# Apollo4-BluePlus-Module_rev_b_v6.net
KiCad netlist of a schematic drawn in EAGLE
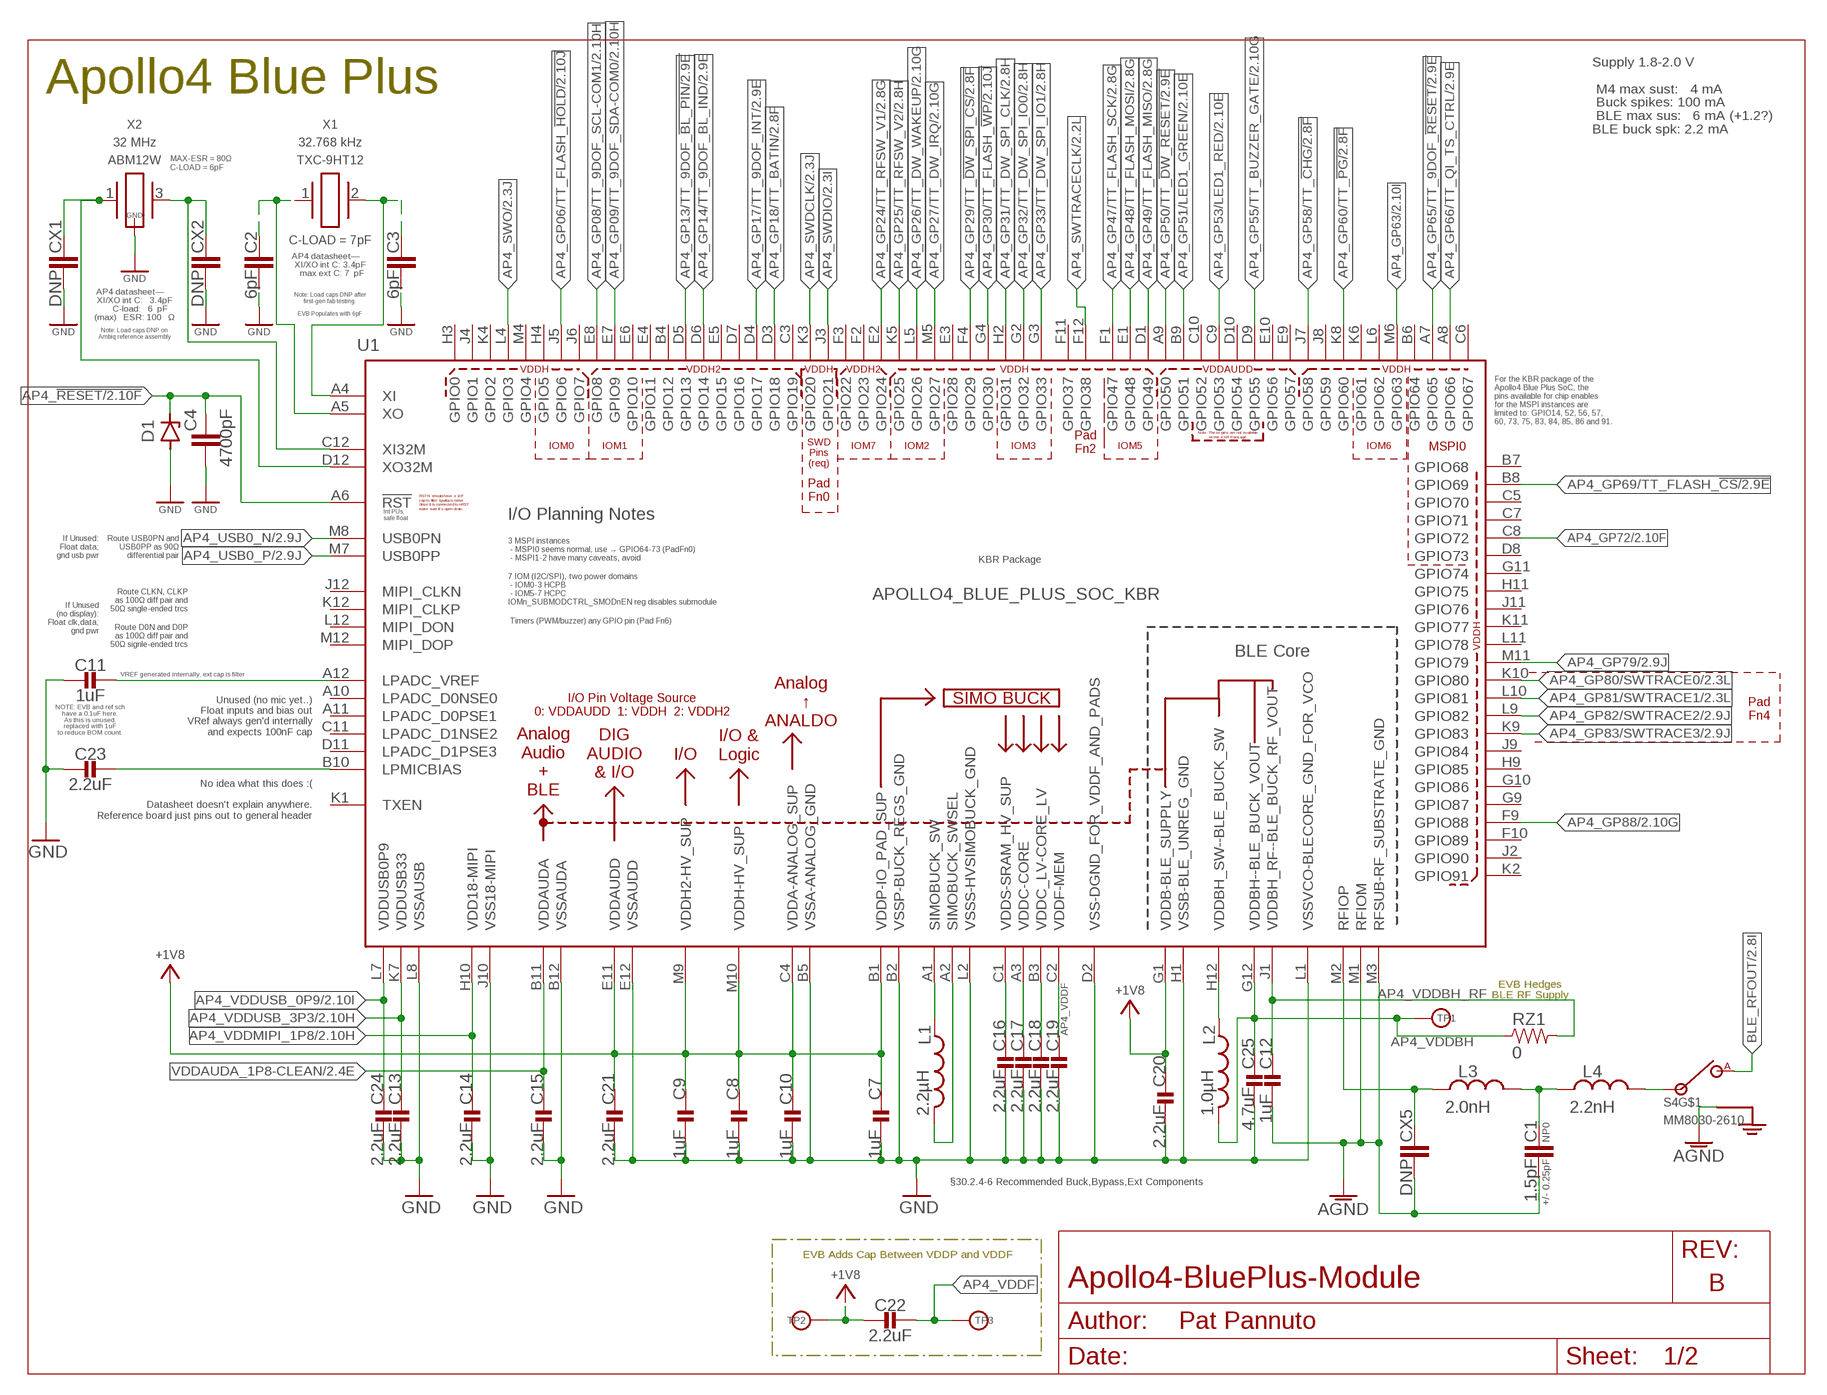
[diagram p0: schematic, sheet 1]
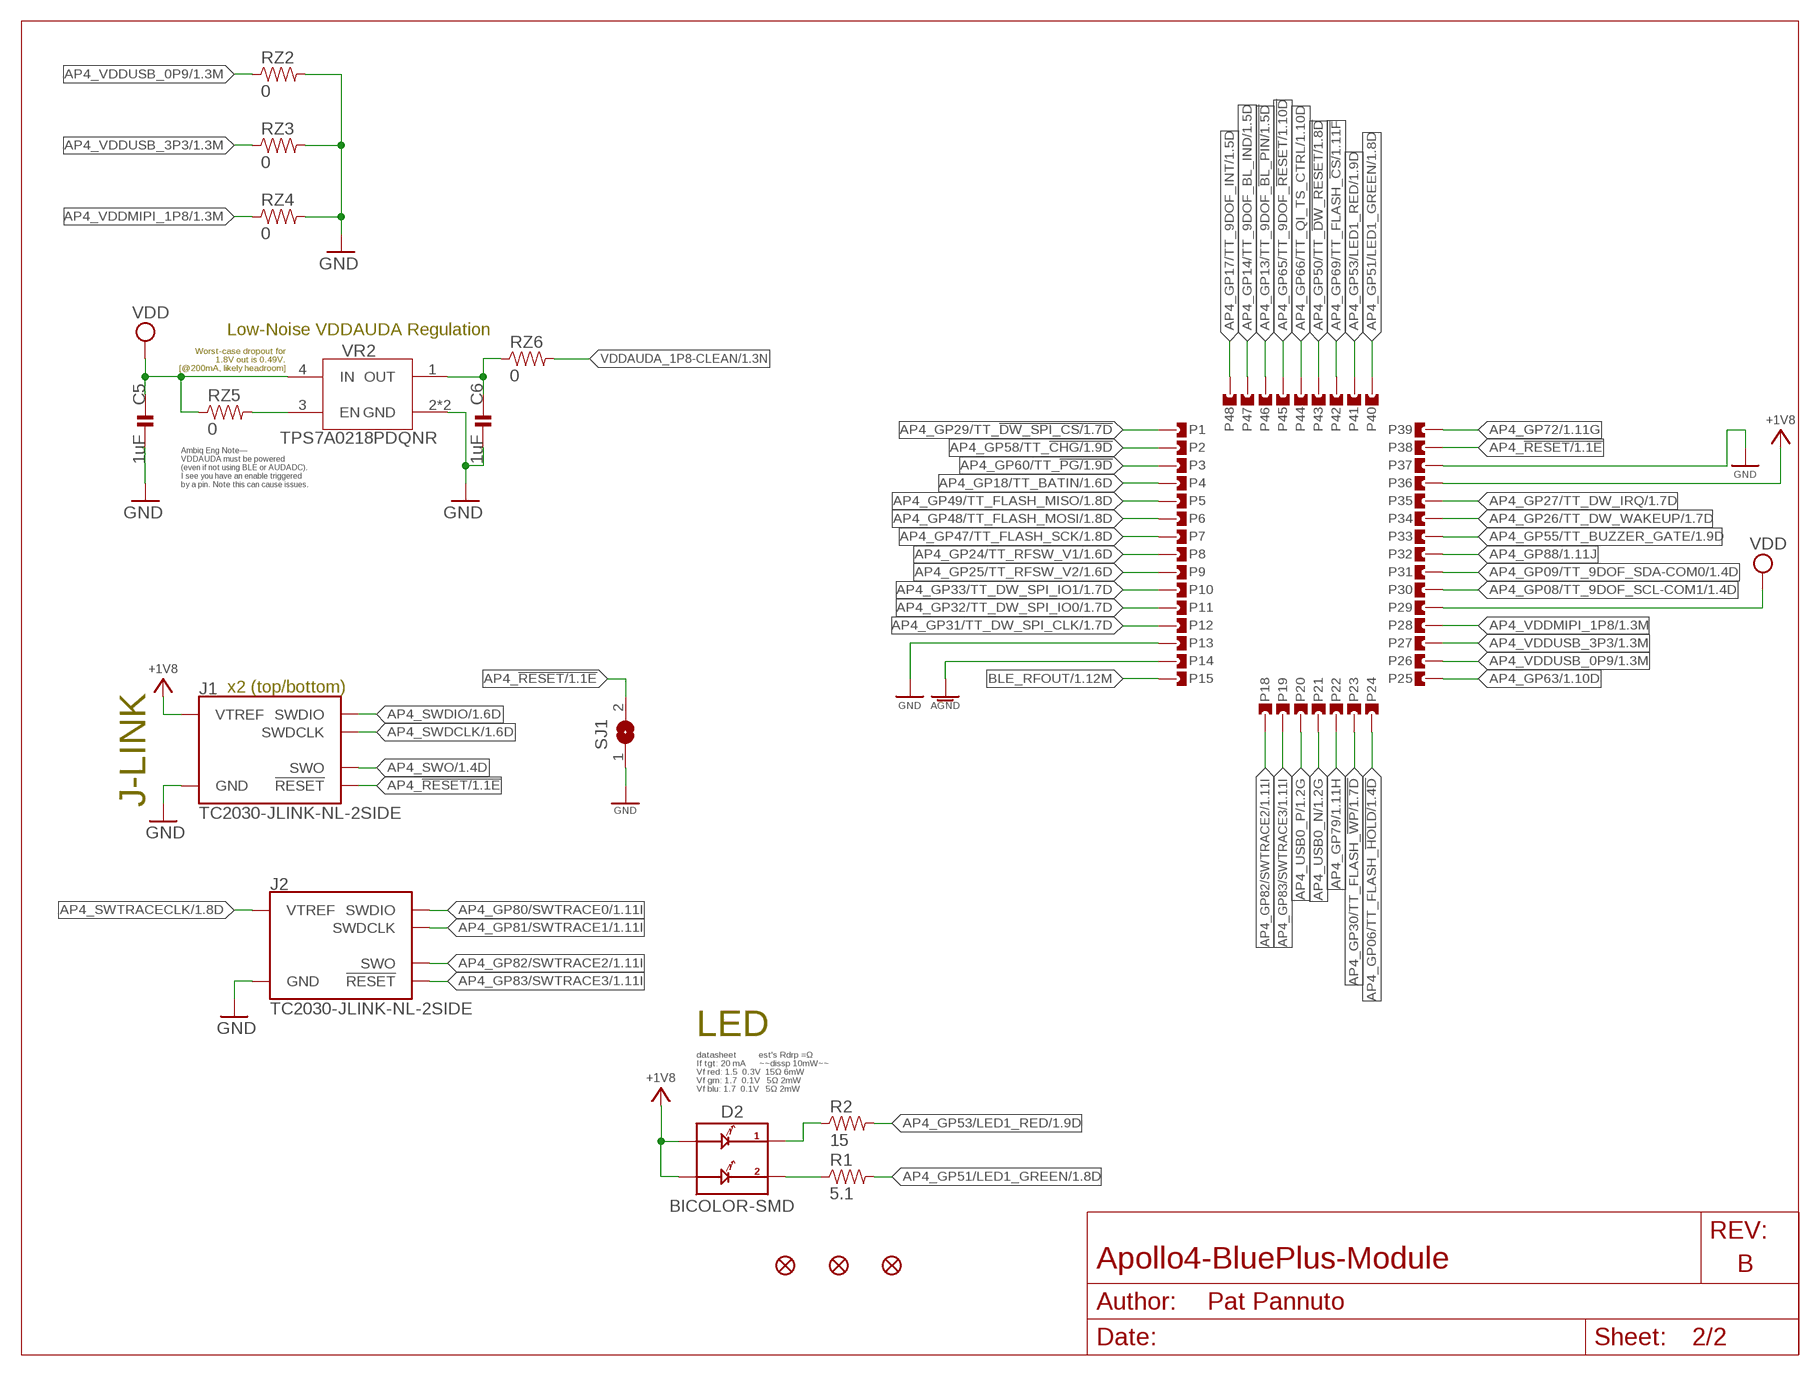
[diagram p1: schematic, sheet 2]

(export (version "E")
  (design (tool "Eeschema 10.0.6"))
  (components
    (comp (ref "C5")
      (value "1uF")
      (footprint "eagle-import:0201_CAP")
      (fields (field (name "MANUFACTURER") "Murata") (field (name "MPN") "GRM033R61A105ME44D"))
      (libsource (lib "eagle-import") (part "passives_20904581_CAPACITOR0201_CAP"))
    )
    (comp (ref "C6")
      (value "1uF")
      (footprint "eagle-import:0201_CAP")
      (fields (field (name "MANUFACTURER") "Murata") (field (name "MPN") "GRM033R61A105ME44D"))
      (libsource (lib "eagle-import") (part "passives_20904581_CAPACITOR0201_CAP"))
    )
    (comp (ref "D2")
      (value "BICOLOR-SMD")
      (footprint "eagle-import:LED-0606")
      (fields (field (name "MPN") "MCL0606FRD1GR1T"))
      (libsource (lib "eagle-import") (part "BICOLOR-SMD"))
    )
    (comp (ref "FD1")
      (value "FIDUCIALUFIDUCIAL")
      (footprint "eagle-import:FIDUCIAL-MICRO")
      (libsource (lib "eagle-import") (part "FIDUCIALUFIDUCIAL"))
    )
    (comp (ref "FD2")
      (value "FIDUCIALUFIDUCIAL")
      (footprint "eagle-import:FIDUCIAL-MICRO")
      (libsource (lib "eagle-import") (part "FIDUCIALUFIDUCIAL"))
    )
    (comp (ref "FD3")
      (value "FIDUCIALUFIDUCIAL")
      (footprint "eagle-import:FIDUCIAL-MICRO")
      (libsource (lib "eagle-import") (part "FIDUCIALUFIDUCIAL"))
    )
    (comp (ref "J1")
      (value "TC2030-JLINK-NL-2SIDE")
      (footprint "eagle-import:TC2030-IDC-NL-2SIDE")
      (libsource (lib "eagle-import") (part "TC2030-JLINK-NL-2SIDE"))
    )
    (comp (ref "J2")
      (value "TC2030-JLINK-NL-2SIDE")
      (footprint "eagle-import:TC2030-IDC-NL-2SIDE")
      (libsource (lib "eagle-import") (part "TC2030-JLINK-NL-2SIDE"))
    )
    (comp (ref "P1")
      (value "CASTELLATION4L")
      (footprint "eagle-import:CASTELLATION-0.55MM_DRILL-4L")
      (libsource (lib "eagle-import") (part "CASTELLATION4L"))
    )
    (comp (ref "P2")
      (value "CASTELLATION4L")
      (footprint "eagle-import:CASTELLATION-0.55MM_DRILL-4L")
      (libsource (lib "eagle-import") (part "CASTELLATION4L"))
    )
    (comp (ref "P3")
      (value "CASTELLATION4L")
      (footprint "eagle-import:CASTELLATION-0.55MM_DRILL-4L")
      (libsource (lib "eagle-import") (part "CASTELLATION4L"))
    )
    (comp (ref "P4")
      (value "CASTELLATION4L")
      (footprint "eagle-import:CASTELLATION-0.55MM_DRILL-4L")
      (libsource (lib "eagle-import") (part "CASTELLATION4L"))
    )
    (comp (ref "P5")
      (value "CASTELLATION4L")
      (footprint "eagle-import:CASTELLATION-0.55MM_DRILL-4L")
      (libsource (lib "eagle-import") (part "CASTELLATION4L"))
    )
    (comp (ref "P6")
      (value "CASTELLATION4L")
      (footprint "eagle-import:CASTELLATION-0.55MM_DRILL-4L")
      (libsource (lib "eagle-import") (part "CASTELLATION4L"))
    )
    (comp (ref "P7")
      (value "CASTELLATION4L")
      (footprint "eagle-import:CASTELLATION-0.55MM_DRILL-4L")
      (libsource (lib "eagle-import") (part "CASTELLATION4L"))
    )
    (comp (ref "P8")
      (value "CASTELLATION4L")
      (footprint "eagle-import:CASTELLATION-0.55MM_DRILL-4L")
      (libsource (lib "eagle-import") (part "CASTELLATION4L"))
    )
    (comp (ref "P9")
      (value "CASTELLATION4L")
      (footprint "eagle-import:CASTELLATION-0.55MM_DRILL-4L")
      (libsource (lib "eagle-import") (part "CASTELLATION4L"))
    )
    (comp (ref "P10")
      (value "CASTELLATION4L")
      (footprint "eagle-import:CASTELLATION-0.55MM_DRILL-4L")
      (libsource (lib "eagle-import") (part "CASTELLATION4L"))
    )
    (comp (ref "P11")
      (value "CASTELLATION4L")
      (footprint "eagle-import:CASTELLATION-0.55MM_DRILL-4L")
      (libsource (lib "eagle-import") (part "CASTELLATION4L"))
    )
    (comp (ref "P12")
      (value "CASTELLATION4L")
      (footprint "eagle-import:CASTELLATION-0.55MM_DRILL-4L")
      (libsource (lib "eagle-import") (part "CASTELLATION4L"))
    )
    (comp (ref "P13")
      (value "CASTELLATION4L")
      (footprint "eagle-import:CASTELLATION-0.55MM_DRILL-4L")
      (libsource (lib "eagle-import") (part "CASTELLATION4L"))
    )
    (comp (ref "P14")
      (value "CASTELLATION4L")
      (footprint "eagle-import:CASTELLATION-0.55MM_DRILL-4L")
      (libsource (lib "eagle-import") (part "CASTELLATION4L"))
    )
    (comp (ref "P15")
      (value "CASTELLATION4L")
      (footprint "eagle-import:CASTELLATION-0.55MM_DRILL-4L")
      (libsource (lib "eagle-import") (part "CASTELLATION4L"))
    )
    (comp (ref "P18")
      (value "CASTELLATION4L")
      (footprint "eagle-import:CASTELLATION-0.55MM_DRILL-4L")
      (libsource (lib "eagle-import") (part "CASTELLATION4L"))
    )
    (comp (ref "P19")
      (value "CASTELLATION4L")
      (footprint "eagle-import:CASTELLATION-0.55MM_DRILL-4L")
      (libsource (lib "eagle-import") (part "CASTELLATION4L"))
    )
    (comp (ref "P20")
      (value "CASTELLATION4L")
      (footprint "eagle-import:CASTELLATION-0.55MM_DRILL-4L")
      (libsource (lib "eagle-import") (part "CASTELLATION4L"))
    )
    (comp (ref "P21")
      (value "CASTELLATION4L")
      (footprint "eagle-import:CASTELLATION-0.55MM_DRILL-4L")
      (libsource (lib "eagle-import") (part "CASTELLATION4L"))
    )
    (comp (ref "P22")
      (value "CASTELLATION4L")
      (footprint "eagle-import:CASTELLATION-0.55MM_DRILL-4L")
      (libsource (lib "eagle-import") (part "CASTELLATION4L"))
    )
    (comp (ref "P23")
      (value "CASTELLATION4L")
      (footprint "eagle-import:CASTELLATION-0.55MM_DRILL-4L")
      (libsource (lib "eagle-import") (part "CASTELLATION4L"))
    )
    (comp (ref "P24")
      (value "CASTELLATION4L")
      (footprint "eagle-import:CASTELLATION-0.55MM_DRILL-4L")
      (libsource (lib "eagle-import") (part "CASTELLATION4L"))
    )
    (comp (ref "P25")
      (value "CASTELLATION4L")
      (footprint "eagle-import:CASTELLATION-0.55MM_DRILL-4L")
      (libsource (lib "eagle-import") (part "CASTELLATION4L"))
    )
    (comp (ref "P26")
      (value "CASTELLATION4L")
      (footprint "eagle-import:CASTELLATION-0.55MM_DRILL-4L")
      (libsource (lib "eagle-import") (part "CASTELLATION4L"))
    )
    (comp (ref "P27")
      (value "CASTELLATION4L")
      (footprint "eagle-import:CASTELLATION-0.55MM_DRILL-4L")
      (libsource (lib "eagle-import") (part "CASTELLATION4L"))
    )
    (comp (ref "P28")
      (value "CASTELLATION4L")
      (footprint "eagle-import:CASTELLATION-0.55MM_DRILL-4L")
      (libsource (lib "eagle-import") (part "CASTELLATION4L"))
    )
    (comp (ref "P29")
      (value "CASTELLATION4L")
      (footprint "eagle-import:CASTELLATION-0.55MM_DRILL-4L")
      (libsource (lib "eagle-import") (part "CASTELLATION4L"))
    )
    (comp (ref "P30")
      (value "CASTELLATION4L")
      (footprint "eagle-import:CASTELLATION-0.55MM_DRILL-4L")
      (libsource (lib "eagle-import") (part "CASTELLATION4L"))
    )
    (comp (ref "P31")
      (value "CASTELLATION4L")
      (footprint "eagle-import:CASTELLATION-0.55MM_DRILL-4L")
      (libsource (lib "eagle-import") (part "CASTELLATION4L"))
    )
    (comp (ref "P32")
      (value "CASTELLATION4L")
      (footprint "eagle-import:CASTELLATION-0.55MM_DRILL-4L")
      (libsource (lib "eagle-import") (part "CASTELLATION4L"))
    )
    (comp (ref "P33")
      (value "CASTELLATION4L")
      (footprint "eagle-import:CASTELLATION-0.55MM_DRILL-4L")
      (libsource (lib "eagle-import") (part "CASTELLATION4L"))
    )
    (comp (ref "P34")
      (value "CASTELLATION4L")
      (footprint "eagle-import:CASTELLATION-0.55MM_DRILL-4L")
      (libsource (lib "eagle-import") (part "CASTELLATION4L"))
    )
    (comp (ref "P35")
      (value "CASTELLATION4L")
      (footprint "eagle-import:CASTELLATION-0.55MM_DRILL-4L")
      (libsource (lib "eagle-import") (part "CASTELLATION4L"))
    )
    (comp (ref "P36")
      (value "CASTELLATION4L")
      (footprint "eagle-import:CASTELLATION-0.55MM_DRILL-4L")
      (libsource (lib "eagle-import") (part "CASTELLATION4L"))
    )
    (comp (ref "P37")
      (value "CASTELLATION4L")
      (footprint "eagle-import:CASTELLATION-0.55MM_DRILL-4L")
      (libsource (lib "eagle-import") (part "CASTELLATION4L"))
    )
    (comp (ref "P38")
      (value "CASTELLATION4L")
      (footprint "eagle-import:CASTELLATION-0.55MM_DRILL-4L")
      (libsource (lib "eagle-import") (part "CASTELLATION4L"))
    )
    (comp (ref "P39")
      (value "CASTELLATION4L")
      (footprint "eagle-import:CASTELLATION-0.55MM_DRILL-4L")
      (libsource (lib "eagle-import") (part "CASTELLATION4L"))
    )
    (comp (ref "P40")
      (value "CASTELLATION4L")
      (footprint "eagle-import:CASTELLATION-0.55MM_DRILL-4L")
      (libsource (lib "eagle-import") (part "CASTELLATION4L"))
    )
    (comp (ref "P41")
      (value "CASTELLATION4L")
      (footprint "eagle-import:CASTELLATION-0.55MM_DRILL-4L")
      (libsource (lib "eagle-import") (part "CASTELLATION4L"))
    )
    (comp (ref "P42")
      (value "CASTELLATION4L")
      (footprint "eagle-import:CASTELLATION-0.55MM_DRILL-4L")
      (libsource (lib "eagle-import") (part "CASTELLATION4L"))
    )
    (comp (ref "P43")
      (value "CASTELLATION4L")
      (footprint "eagle-import:CASTELLATION-0.55MM_DRILL-4L")
      (libsource (lib "eagle-import") (part "CASTELLATION4L"))
    )
    (comp (ref "P44")
      (value "CASTELLATION4L")
      (footprint "eagle-import:CASTELLATION-0.55MM_DRILL-4L")
      (libsource (lib "eagle-import") (part "CASTELLATION4L"))
    )
    (comp (ref "P45")
      (value "CASTELLATION4L")
      (footprint "eagle-import:CASTELLATION-0.55MM_DRILL-4L")
      (libsource (lib "eagle-import") (part "CASTELLATION4L"))
    )
    (comp (ref "P46")
      (value "CASTELLATION4L")
      (footprint "eagle-import:CASTELLATION-0.55MM_DRILL-4L")
      (libsource (lib "eagle-import") (part "CASTELLATION4L"))
    )
    (comp (ref "P47")
      (value "CASTELLATION4L")
      (footprint "eagle-import:CASTELLATION-0.55MM_DRILL-4L")
      (libsource (lib "eagle-import") (part "CASTELLATION4L"))
    )
    (comp (ref "P48")
      (value "CASTELLATION4L")
      (footprint "eagle-import:CASTELLATION-0.55MM_DRILL-4L")
      (libsource (lib "eagle-import") (part "CASTELLATION4L"))
    )
    (comp (ref "R1")
      (value "5.1")
      (footprint "eagle-import:0201_RES")
      (fields (field (name "MPN") "SR731HTTC5R10F"))
      (libsource (lib "eagle-import") (part "RESISTOR0201_RES"))
    )
    (comp (ref "R2")
      (value "15")
      (footprint "eagle-import:0201_RES")
      (description "RES SMD 15 OHM 5% 1/20W 0201")
      (fields (field (name "MPN") "ERJ-1GNJ150C"))
      (libsource (lib "eagle-import") (part "RESISTOR0201_RES"))
    )
    (comp (ref "RZ2")
      (value "0")
      (footprint "eagle-import:0402_RES")
      (fields (field (name "MPN") "RMCF0402ZT0R00"))
      (libsource (lib "eagle-import") (part "RESISTOR0402_RES"))
    )
    (comp (ref "RZ3")
      (value "0")
      (footprint "eagle-import:0402_RES")
      (fields (field (name "MPN") "RMCF0402ZT0R00"))
      (libsource (lib "eagle-import") (part "RESISTOR0402_RES"))
    )
    (comp (ref "RZ4")
      (value "0")
      (footprint "eagle-import:0402_RES")
      (fields (field (name "MPN") "RMCF0402ZT0R00"))
      (libsource (lib "eagle-import") (part "RESISTOR0402_RES"))
    )
    (comp (ref "RZ5")
      (value "0")
      (footprint "eagle-import:0402_RES")
      (fields (field (name "MPN") "RMCF0402ZT0R00"))
      (libsource (lib "eagle-import") (part "RESISTOR0402_RES"))
    )
    (comp (ref "RZ6")
      (value "0")
      (footprint "eagle-import:0402_RES")
      (fields (field (name "MPN") "RMCF0402ZT0R00"))
      (libsource (lib "eagle-import") (part "RESISTOR0402_RES"))
    )
    (comp (ref "SJ1") (value "SJ") (footprint "eagle-import:SJ") (libsource (lib "eagle-import") (part "SJ")))
    (comp (ref "VR2")
      (value "TPS7A0218PDQNR")
      (footprint "eagle-import:4-XDFN-EP")
      (libsource (lib "eagle-import") (part "TPS7A0218PDQNR"))
    )
    (comp (ref "C1")
      (value "1.5pF")
      (footprint "eagle-import:CAPC1005X60")
      (description "CAP CER 1.5PF 50V C0G/NP0 0402")
      (fields
        (field (name "MANUFACTURER") "KEMET")
        (field (name "MPN") "C0402C159C5GAC7867")
        (field (name "TEMPCOEFF") "NP0")
        (field (name "TOLERANCE") "+/- 0.25pF")
      )
      (libsource (lib "eagle-import") (part "CCHIP-0402(1005-METRIC)_"))
    )
    (comp (ref "C2")
      (value "6pF")
      (footprint "eagle-import:CAPC1005X60")
      (fields (field (name "MANUFACTURER") "Murata") (field (name "MPN") "GCM1555C1H6R0BA16D"))
      (libsource (lib "eagle-import") (part "CCHIP-0402(1005-METRIC)_"))
    )
    (comp (ref "C3")
      (value "6pF")
      (footprint "eagle-import:CAPC1005X60")
      (fields (field (name "MANUFACTURER") "Murata") (field (name "MPN") "GCM1555C1H6R0BA16D"))
      (libsource (lib "eagle-import") (part "CCHIP-0402(1005-METRIC)_"))
    )
    (comp (ref "C4")
      (value "4700pF")
      (footprint "eagle-import:CAPC1005X60")
      (fields (field (name "MPN") "KGM05AR71E472KH"))
      (libsource (lib "eagle-import") (part "CCHIP-0402(1005-METRIC)_"))
    )
    (comp (ref "C7")
      (value "1uF")
      (footprint "eagle-import:0201_CAP")
      (fields (field (name "MANUFACTURER") "Murata") (field (name "MPN") "GRM033R61A105ME44D"))
      (libsource (lib "eagle-import") (part "passives_20904581_CAPACITOR0201_CAP"))
    )
    (comp (ref "C8")
      (value "1uF")
      (footprint "eagle-import:0201_CAP")
      (fields (field (name "MANUFACTURER") "Murata") (field (name "MPN") "GRM033R61A105ME44D"))
      (libsource (lib "eagle-import") (part "passives_20904581_CAPACITOR0201_CAP"))
    )
    (comp (ref "C9")
      (value "1uF")
      (footprint "eagle-import:0201_CAP")
      (fields (field (name "MANUFACTURER") "Murata") (field (name "MPN") "GRM033R61A105ME44D"))
      (libsource (lib "eagle-import") (part "passives_20904581_CAPACITOR0201_CAP"))
    )
    (comp (ref "C10")
      (value "1uF")
      (footprint "eagle-import:0201_CAP")
      (fields (field (name "MANUFACTURER") "Murata") (field (name "MPN") "GRM033R61A105ME44D"))
      (libsource (lib "eagle-import") (part "passives_20904581_CAPACITOR0201_CAP"))
    )
    (comp (ref "C11")
      (value "1uF")
      (footprint "eagle-import:0201_CAP")
      (fields (field (name "MANUFACTURER") "MURATA") (field (name "MPN") "GRM033R61A105ME44D"))
      (libsource (lib "eagle-import") (part "passives_20904581_CAPACITOR0201_CAP"))
    )
    (comp (ref "C12")
      (value "1uF")
      (footprint "eagle-import:0201_CAP")
      (fields (field (name "MANUFACTURER") "Murata") (field (name "MPN") "GRM033R61A105ME44D"))
      (libsource (lib "eagle-import") (part "passives_20904581_CAPACITOR0201_CAP"))
    )
    (comp (ref "C13")
      (value "2.2uF")
      (footprint "eagle-import:0201_CAP")
      (fields (field (name "MANUFACTURER") "Murata") (field (name "MPN") "GRM033R61A225KE47D"))
      (libsource (lib "eagle-import") (part "passives_20904581_CAPACITOR0201_CAP"))
    )
    (comp (ref "C14")
      (value "2.2uF")
      (footprint "eagle-import:0201_CAP")
      (fields (field (name "MANUFACTURER") "Murata") (field (name "MPN") "GRM033R61A225KE47D"))
      (libsource (lib "eagle-import") (part "passives_20904581_CAPACITOR0201_CAP"))
    )
    (comp (ref "C15")
      (value "2.2uF")
      (footprint "eagle-import:0201_CAP")
      (fields (field (name "MANUFACTURER") "Murata") (field (name "MPN") "GRM033R61A225KE47D"))
      (libsource (lib "eagle-import") (part "passives_20904581_CAPACITOR0201_CAP"))
    )
    (comp (ref "C16")
      (value "2.2uF")
      (footprint "eagle-import:0201_CAP")
      (fields (field (name "MANUFACTURER") "Murata") (field (name "MPN") "GRM033R61A225KE47D"))
      (libsource (lib "eagle-import") (part "passives_20904581_CAPACITOR0201_CAP"))
    )
    (comp (ref "C17")
      (value "2.2uF")
      (footprint "eagle-import:0201_CAP")
      (fields (field (name "MANUFACTURER") "Murata") (field (name "MPN") "GRM033R61A225KE47D"))
      (libsource (lib "eagle-import") (part "passives_20904581_CAPACITOR0201_CAP"))
    )
    (comp (ref "C18")
      (value "2.2uF")
      (footprint "eagle-import:0201_CAP")
      (fields (field (name "MANUFACTURER") "Murata") (field (name "MPN") "GRM033R61A225KE47D"))
      (libsource (lib "eagle-import") (part "passives_20904581_CAPACITOR0201_CAP"))
    )
    (comp (ref "C19")
      (value "2.2uF")
      (footprint "eagle-import:0201_CAP")
      (fields (field (name "MANUFACTURER") "Murata") (field (name "MPN") "GRM033R61A225KE47D"))
      (libsource (lib "eagle-import") (part "passives_20904581_CAPACITOR0201_CAP"))
    )
    (comp (ref "C20")
      (value "2.2uF")
      (footprint "eagle-import:0201_CAP")
      (fields (field (name "MANUFACTURER") "Murata") (field (name "MPN") "GRM033R61A225KE47D"))
      (libsource (lib "eagle-import") (part "passives_20904581_CAPACITOR0201_CAP"))
    )
    (comp (ref "C21")
      (value "2.2uF")
      (footprint "eagle-import:0201_CAP")
      (fields (field (name "MANUFACTURER") "Murata") (field (name "MPN") "GRM033R61A225KE47D"))
      (libsource (lib "eagle-import") (part "passives_20904581_CAPACITOR0201_CAP"))
    )
    (comp (ref "C22")
      (value "2.2uF")
      (footprint "eagle-import:0201_CAP")
      (fields (field (name "MANUFACTURER") "Murata") (field (name "MPN") "GRM033R61A225KE47D"))
      (libsource (lib "eagle-import") (part "passives_20904581_CAPACITOR0201_CAP"))
    )
    (comp (ref "C23")
      (value "2.2uF")
      (footprint "eagle-import:0201_CAP")
      (fields (field (name "MANUFACTURER") "Murata") (field (name "MPN") "GRM033R61A225KE47D"))
      (libsource (lib "eagle-import") (part "passives_20904581_CAPACITOR0201_CAP"))
    )
    (comp (ref "C24")
      (value "2.2uF")
      (footprint "eagle-import:0201_CAP")
      (fields (field (name "MANUFACTURER") "Murata") (field (name "MPN") "GRM033R61A225KE47D"))
      (libsource (lib "eagle-import") (part "passives_20904581_CAPACITOR0201_CAP"))
    )
    (comp (ref "C25")
      (value "4.7uF")
      (footprint "eagle-import:0402_CAP")
      (fields (field (name "MPN") "CL05A475MP5NRNC"))
      (libsource (lib "eagle-import") (part "CAPACITOR0402_CAP"))
    )
    (comp (ref "CX1")
      (value "DNP")
      (footprint "eagle-import:CAPC1005X60")
      (libsource (lib "eagle-import") (part "CCHIP-0402(1005-METRIC)_"))
    )
    (comp (ref "CX2")
      (value "DNP")
      (footprint "eagle-import:CAPC1005X60")
      (libsource (lib "eagle-import") (part "CCHIP-0402(1005-METRIC)_"))
    )
    (comp (ref "CX5")
      (value "DNP")
      (footprint "eagle-import:CAPC1005X60")
      (libsource (lib "eagle-import") (part "CCHIP-0402(1005-METRIC)_"))
    )
    (comp (ref "D1")
      (value "ZENER")
      (footprint "eagle-import:SODFL1608X70")
      (description "DIODE TVS 5.5V STANDOFF 8V BREAKDOWN SC79")
      (fields (field (name "MANUFACTURER") "NXP SEMICONDUCTOR") (field (name "MPN") "PESD5V0X1UB,135"))
      (libsource (lib "eagle-import") (part "ZENERSODFL(1608-METRIC)_"))
    )
    (comp (ref "L1")
      (value "2.2µH")
      (footprint "eagle-import:0805_CAP")
      (fields (field (name "MANUFACTURER") "Murata") (field (name "MPN") "DFE201210U-2R2M=P2"))
      (libsource (lib "eagle-import") (part "INDUCTOR0805"))
    )
    (comp (ref "L2")
      (value "1.0µH")
      (footprint "eagle-import:0603_CAP")
      (fields (field (name "MANUFACTURER") "Murata") (field (name "MPN") "DFE18SAN1R0ME0L"))
      (libsource (lib "eagle-import") (part "INDUCTOR0603"))
    )
    (comp (ref "L3")
      (value "2.0nH")
      (footprint "eagle-import:INDC1006X60N")
      (description "FIXED IND 2.0NH0.1NH SMD")
      (fields
        (field (name "MANUFACTURER") "Central Technologies")
        (field (name "MPN") "CTTF0402F-2N0B")
        (field (name "TOLERANCE") "+/- 0.1 nH")
      )
      (libsource (lib "eagle-import") (part "LCHIP-0402(1006-METRIC)_"))
    )
    (comp (ref "L4")
      (value "2.2nH")
      (footprint "eagle-import:INDC1006X60N")
      (description "FIXED IND 2.2NH0.1NH SMD")
      (fields
        (field (name "MANUFACTURER") "Central Technologies")
        (field (name "MPN") "CTTF0402F-2N2B")
        (field (name "TOLERANCE") "+/- 0.1 nH")
      )
      (libsource (lib "eagle-import") (part "LCHIP-0402(1006-METRIC)_"))
    )
    (comp (ref "RZ1")
      (value "0")
      (footprint "eagle-import:0402_RES")
      (fields (field (name "MPN") "RMCF0402ZT0R00"))
      (libsource (lib "eagle-import") (part "RESISTOR0402_RES"))
    )
    (comp (ref "S4")
      (value "MM8030-2610")
      (footprint "eagle-import:MM8030-2610")
      (fields (field (name "MANUFACTURER") "Murata"))
      (libsource (lib "eagle-import") (part "MM8030-2610"))
    )
    (comp (ref "TP1")
      (value "VDDBH")
      (footprint "eagle-import:PAD.03X.03")
      (libsource (lib "eagle-import") (part "TEST-POINT"))
    )
    (comp (ref "TP2")
      (value "VDDP")
      (footprint "eagle-import:PAD.03X.03")
      (libsource (lib "eagle-import") (part "TEST-POINT"))
    )
    (comp (ref "TP3")
      (value "VDDF")
      (footprint "eagle-import:PAD.03X.03")
      (libsource (lib "eagle-import") (part "TEST-POINT"))
    )
    (comp (ref "U1")
      (value "APOLLO4_BLUE_PLUS_SOC_KBR")
      (footprint "eagle-import:APOLLO4_BLUE_SOC_BGA")
      (fields (field (name "MANUFACTURER") "Ambiq") (field (name "MPN") "AMA4B2KP-KBR"))
      (libsource (lib "eagle-import") (part "APOLLO4_BLUE_PLUS_SOC_KBR"))
    )
    (comp (ref "X1")
      (value "TXC-9HT12")
      (footprint "eagle-import:TXC-9HT12")
      (fields
        (field (name "C-LOAD") "7pF")
        (field (name "FREQUENCY") "32.768 kHz")
        (field (name "MANUFACTURER") "TXC Corp")
        (field (name "MPN") "9HT12-32.768KDZY-T")
      )
      (libsource (lib "eagle-import") (part "TXC-9HT12"))
    )
    (comp (ref "X2")
      (value "ABM12W")
      (footprint "eagle-import:ABM12W")
      (fields
        (field (name "C-LOAD") "6pF")
        (field (name "FREQUENCY") "32 MHz")
        (field (name "MANUFACTURER") "Abracon")
        (field (name "MAX-ESR") "80Ω")
        (field (name "MPN") "ABM12W-32.0000MHZ-6-D1X-T3")
      )
      (libsource (lib "eagle-import") (part "ABM12W"))
    )
  )
  (nets
    (net (code "1") (name "+1V8") (class "Default")
      (node (ref "C10") (pin "P$1") (pinfunction "1_P$1") (pintype "bidirectional"))
      (node (ref "C20") (pin "P$1") (pinfunction "1_P$1") (pintype "bidirectional"))
      (node (ref "C21") (pin "P$1") (pinfunction "1_P$1") (pintype "bidirectional"))
      (node (ref "C22") (pin "P$2") (pinfunction "2_P$2") (pintype "bidirectional"))
      (node (ref "C7") (pin "P$1") (pinfunction "1_P$1") (pintype "bidirectional"))
      (node (ref "C8") (pin "P$1") (pinfunction "1_P$1") (pintype "bidirectional"))
      (node (ref "C9") (pin "P$1") (pinfunction "1_P$1") (pintype "bidirectional"))
      (node (ref "D2") (pin "A1") (pinfunction "A1_A1") (pintype "bidirectional"))
      (node (ref "D2") (pin "A2") (pinfunction "A2_A2") (pintype "bidirectional"))
      (node (ref "J1") (pin "1") (pinfunction "VTREF_1") (pintype "bidirectional"))
      (node (ref "J1") (pin "B1") (pinfunction "VTREF_B1") (pintype "bidirectional"))
      (node (ref "P36") (pin "P$1") (pinfunction "P$1_P$1") (pintype "bidirectional"))
      (node (ref "P36") (pin "P$2") (pinfunction "P$1_P$2") (pintype "bidirectional"))
      (node (ref "P36") (pin "P$3") (pinfunction "P$1_P$3") (pintype "bidirectional"))
      (node (ref "TP2") (pin "P$1") (pinfunction "TESTPOINT_P$1") (pintype "bidirectional"))
      (node (ref "U1") (pin "B1") (pinfunction "VDDP-IO_PAD_SUP_B1") (pintype "bidirectional"))
      (node (ref "U1") (pin "C4") (pinfunction "VDDA-ANALOG_SUP_C4") (pintype "bidirectional"))
      (node (ref "U1") (pin "E11") (pinfunction "VDDAUDD_E11") (pintype "bidirectional"))
      (node (ref "U1") (pin "G1") (pinfunction "VDDB-BLE_SUPPLY_G1") (pintype "bidirectional"))
      (node (ref "U1") (pin "M10") (pinfunction "VDDH-HV_SUP_M10") (pintype "bidirectional"))
      (node (ref "U1") (pin "M9") (pinfunction "VDDH2-HV_SUP_M9") (pintype "bidirectional"))
    )
    (net (code "2") (name "AGND") (class "Default")
      (node (ref "C1") (pin "2") (pinfunction "2_2") (pintype "passive"))
      (node (ref "C12") (pin "P$2") (pinfunction "2_P$2") (pintype "bidirectional"))
      (node (ref "CX5") (pin "2") (pinfunction "2_2") (pintype "passive"))
      (node (ref "P14") (pin "P$1") (pinfunction "P$1_P$1") (pintype "bidirectional"))
      (node (ref "P14") (pin "P$2") (pinfunction "P$1_P$2") (pintype "bidirectional"))
      (node (ref "P14") (pin "P$3") (pinfunction "P$1_P$3") (pintype "bidirectional"))
      (node (ref "S4") (pin "G1") (pinfunction "GND_G1") (pintype "bidirectional"))
      (node (ref "S4") (pin "G2") (pinfunction "GND_G2") (pintype "bidirectional"))
      (node (ref "U1") (pin "M1") (pinfunction "RFIOM_M1") (pintype "bidirectional"))
      (node (ref "U1") (pin "M3") (pinfunction "RFSUB-RF_SUBSTRATE_GND_M3") (pintype "bidirectional"))
    )
    (net (code "3") (name "AP4_GP06{slash}TT_FLASH_~{HOLD}") (class "Default")
      (node (ref "P24") (pin "P$1") (pinfunction "P$1_P$1") (pintype "bidirectional"))
      (node (ref "P24") (pin "P$2") (pinfunction "P$1_P$2") (pintype "bidirectional"))
      (node (ref "P24") (pin "P$3") (pinfunction "P$1_P$3") (pintype "bidirectional"))
      (node (ref "U1") (pin "J5") (pinfunction "GPIO6_J5") (pintype "bidirectional"))
    )
    (net (code "4") (name "AP4_GP08{slash}TT_9DOF_SCL-COM1") (class "Default")
      (node (ref "P30") (pin "P$1") (pinfunction "P$1_P$1") (pintype "bidirectional"))
      (node (ref "P30") (pin "P$2") (pinfunction "P$1_P$2") (pintype "bidirectional"))
      (node (ref "P30") (pin "P$3") (pinfunction "P$1_P$3") (pintype "bidirectional"))
      (node (ref "U1") (pin "E8") (pinfunction "GPIO8_E8") (pintype "bidirectional"))
    )
    (net (code "5") (name "AP4_GP09{slash}TT_9DOF_SDA-COM0") (class "Default")
      (node (ref "P31") (pin "P$1") (pinfunction "P$1_P$1") (pintype "bidirectional"))
      (node (ref "P31") (pin "P$2") (pinfunction "P$1_P$2") (pintype "bidirectional"))
      (node (ref "P31") (pin "P$3") (pinfunction "P$1_P$3") (pintype "bidirectional"))
      (node (ref "U1") (pin "E7") (pinfunction "GPIO9_E7") (pintype "bidirectional"))
    )
    (net (code "6") (name "AP4_GP13{slash}TT_9DOF_~{BL_PIN}") (class "Default")
      (node (ref "P46") (pin "P$1") (pinfunction "P$1_P$1") (pintype "bidirectional"))
      (node (ref "P46") (pin "P$2") (pinfunction "P$1_P$2") (pintype "bidirectional"))
      (node (ref "P46") (pin "P$3") (pinfunction "P$1_P$3") (pintype "bidirectional"))
      (node (ref "U1") (pin "D5") (pinfunction "GPIO13_D5") (pintype "bidirectional"))
    )
    (net (code "7") (name "AP4_GP14{slash}TT_9DOF_BL_IND") (class "Default")
      (node (ref "P47") (pin "P$1") (pinfunction "P$1_P$1") (pintype "bidirectional"))
      (node (ref "P47") (pin "P$2") (pinfunction "P$1_P$2") (pintype "bidirectional"))
      (node (ref "P47") (pin "P$3") (pinfunction "P$1_P$3") (pintype "bidirectional"))
      (node (ref "U1") (pin "D6") (pinfunction "GPIO14_D6") (pintype "bidirectional"))
    )
    (net (code "8") (name "AP4_GP17{slash}TT_9DOF_INT") (class "Default")
      (node (ref "P48") (pin "P$1") (pinfunction "P$1_P$1") (pintype "bidirectional"))
      (node (ref "P48") (pin "P$2") (pinfunction "P$1_P$2") (pintype "bidirectional"))
      (node (ref "P48") (pin "P$3") (pinfunction "P$1_P$3") (pintype "bidirectional"))
      (node (ref "U1") (pin "D4") (pinfunction "GPIO17_D4") (pintype "bidirectional"))
    )
    (net (code "9") (name "AP4_GP18{slash}TT_BATIN") (class "Default")
      (node (ref "P4") (pin "P$1") (pinfunction "P$1_P$1") (pintype "bidirectional"))
      (node (ref "P4") (pin "P$2") (pinfunction "P$1_P$2") (pintype "bidirectional"))
      (node (ref "P4") (pin "P$3") (pinfunction "P$1_P$3") (pintype "bidirectional"))
      (node (ref "U1") (pin "D3") (pinfunction "GPIO18_D3") (pintype "bidirectional"))
    )
    (net (code "10") (name "AP4_GP24{slash}TT_RFSW_V1") (class "Default")
      (node (ref "P8") (pin "P$1") (pinfunction "P$1_P$1") (pintype "bidirectional"))
      (node (ref "P8") (pin "P$2") (pinfunction "P$1_P$2") (pintype "bidirectional"))
      (node (ref "P8") (pin "P$3") (pinfunction "P$1_P$3") (pintype "bidirectional"))
      (node (ref "U1") (pin "E2") (pinfunction "GPIO24_E2") (pintype "bidirectional"))
    )
    (net (code "11") (name "AP4_GP25{slash}TT_RFSW_V2") (class "Default")
      (node (ref "P9") (pin "P$1") (pinfunction "P$1_P$1") (pintype "bidirectional"))
      (node (ref "P9") (pin "P$2") (pinfunction "P$1_P$2") (pintype "bidirectional"))
      (node (ref "P9") (pin "P$3") (pinfunction "P$1_P$3") (pintype "bidirectional"))
      (node (ref "U1") (pin "K5") (pinfunction "GPIO25_K5") (pintype "bidirectional"))
    )
    (net (code "12") (name "AP4_GP26{slash}TT_DW_WAKEUP") (class "Default")
      (node (ref "P34") (pin "P$1") (pinfunction "P$1_P$1") (pintype "bidirectional"))
      (node (ref "P34") (pin "P$2") (pinfunction "P$1_P$2") (pintype "bidirectional"))
      (node (ref "P34") (pin "P$3") (pinfunction "P$1_P$3") (pintype "bidirectional"))
      (node (ref "U1") (pin "L5") (pinfunction "GPIO26_L5") (pintype "bidirectional"))
    )
    (net (code "13") (name "AP4_GP27{slash}TT_DW_IRQ") (class "Default")
      (node (ref "P35") (pin "P$1") (pinfunction "P$1_P$1") (pintype "bidirectional"))
      (node (ref "P35") (pin "P$2") (pinfunction "P$1_P$2") (pintype "bidirectional"))
      (node (ref "P35") (pin "P$3") (pinfunction "P$1_P$3") (pintype "bidirectional"))
      (node (ref "U1") (pin "M5") (pinfunction "GPIO27_M5") (pintype "bidirectional"))
    )
    (net (code "14") (name "AP4_GP29{slash}TT_~{DW_SPI_CS}") (class "Default")
      (node (ref "P1") (pin "P$1") (pinfunction "P$1_P$1") (pintype "bidirectional"))
      (node (ref "P1") (pin "P$2") (pinfunction "P$1_P$2") (pintype "bidirectional"))
      (node (ref "P1") (pin "P$3") (pinfunction "P$1_P$3") (pintype "bidirectional"))
      (node (ref "U1") (pin "F4") (pinfunction "GPIO29_F4") (pintype "bidirectional"))
    )
    (net (code "15") (name "AP4_GP30{slash}TT_FLASH_~{WP}") (class "Default")
      (node (ref "P23") (pin "P$1") (pinfunction "P$1_P$1") (pintype "bidirectional"))
      (node (ref "P23") (pin "P$2") (pinfunction "P$1_P$2") (pintype "bidirectional"))
      (node (ref "P23") (pin "P$3") (pinfunction "P$1_P$3") (pintype "bidirectional"))
      (node (ref "U1") (pin "G4") (pinfunction "GPIO30_G4") (pintype "bidirectional"))
    )
    (net (code "16") (name "AP4_GP31{slash}TT_DW_SPI_CLK") (class "Default")
      (node (ref "P12") (pin "P$1") (pinfunction "P$1_P$1") (pintype "bidirectional"))
      (node (ref "P12") (pin "P$2") (pinfunction "P$1_P$2") (pintype "bidirectional"))
      (node (ref "P12") (pin "P$3") (pinfunction "P$1_P$3") (pintype "bidirectional"))
      (node (ref "U1") (pin "H2") (pinfunction "GPIO31_H2") (pintype "bidirectional"))
    )
    (net (code "17") (name "AP4_GP32{slash}TT_DW_SPI_IO0") (class "Default")
      (node (ref "P11") (pin "P$1") (pinfunction "P$1_P$1") (pintype "bidirectional"))
      (node (ref "P11") (pin "P$2") (pinfunction "P$1_P$2") (pintype "bidirectional"))
      (node (ref "P11") (pin "P$3") (pinfunction "P$1_P$3") (pintype "bidirectional"))
      (node (ref "U1") (pin "G2") (pinfunction "GPIO32_G2") (pintype "bidirectional"))
    )
    (net (code "18") (name "AP4_GP33{slash}TT_DW_SPI_IO1") (class "Default")
      (node (ref "P10") (pin "P$1") (pinfunction "P$1_P$1") (pintype "bidirectional"))
      (node (ref "P10") (pin "P$2") (pinfunction "P$1_P$2") (pintype "bidirectional"))
      (node (ref "P10") (pin "P$3") (pinfunction "P$1_P$3") (pintype "bidirectional"))
      (node (ref "U1") (pin "G3") (pinfunction "GPIO33_G3") (pintype "bidirectional"))
    )
    (net (code "19") (name "AP4_GP47{slash}TT_FLASH_SCK") (class "Default")
      (node (ref "P7") (pin "P$1") (pinfunction "P$1_P$1") (pintype "bidirectional"))
      (node (ref "P7") (pin "P$2") (pinfunction "P$1_P$2") (pintype "bidirectional"))
      (node (ref "P7") (pin "P$3") (pinfunction "P$1_P$3") (pintype "bidirectional"))
      (node (ref "U1") (pin "F1") (pinfunction "GPIO47_F1") (pintype "bidirectional"))
    )
    (net (code "20") (name "AP4_GP48{slash}TT_FLASH_MOSI") (class "Default")
      (node (ref "P6") (pin "P$1") (pinfunction "P$1_P$1") (pintype "bidirectional"))
      (node (ref "P6") (pin "P$2") (pinfunction "P$1_P$2") (pintype "bidirectional"))
      (node (ref "P6") (pin "P$3") (pinfunction "P$1_P$3") (pintype "bidirectional"))
      (node (ref "U1") (pin "E1") (pinfunction "GPIO48_E1") (pintype "bidirectional"))
    )
    (net (code "21") (name "AP4_GP49{slash}TT_FLASH_MISO") (class "Default")
      (node (ref "P5") (pin "P$1") (pinfunction "P$1_P$1") (pintype "bidirectional"))
      (node (ref "P5") (pin "P$2") (pinfunction "P$1_P$2") (pintype "bidirectional"))
      (node (ref "P5") (pin "P$3") (pinfunction "P$1_P$3") (pintype "bidirectional"))
      (node (ref "U1") (pin "D1") (pinfunction "GPIO49_D1") (pintype "bidirectional"))
    )
    (net (code "22") (name "AP4_GP50{slash}TT_~{DW_RESET}") (class "Default")
      (node (ref "P43") (pin "P$1") (pinfunction "P$1_P$1") (pintype "bidirectional"))
      (node (ref "P43") (pin "P$2") (pinfunction "P$1_P$2") (pintype "bidirectional"))
      (node (ref "P43") (pin "P$3") (pinfunction "P$1_P$3") (pintype "bidirectional"))
      (node (ref "U1") (pin "A9") (pinfunction "GPIO50_A9") (pintype "bidirectional"))
    )
    (net (code "23") (name "AP4_GP51{slash}LED1_GREEN") (class "Default")
      (node (ref "P40") (pin "P$1") (pinfunction "P$1_P$1") (pintype "bidirectional"))
      (node (ref "P40") (pin "P$2") (pinfunction "P$1_P$2") (pintype "bidirectional"))
      (node (ref "P40") (pin "P$3") (pinfunction "P$1_P$3") (pintype "bidirectional"))
      (node (ref "R1") (pin "2") (pinfunction "2_2") (pintype "passive"))
      (node (ref "U1") (pin "B9") (pinfunction "GPIO51_B9") (pintype "bidirectional"))
    )
    (net (code "24") (name "AP4_GP53{slash}LED1_RED") (class "Default")
      (node (ref "P41") (pin "P$1") (pinfunction "P$1_P$1") (pintype "bidirectional"))
      (node (ref "P41") (pin "P$2") (pinfunction "P$1_P$2") (pintype "bidirectional"))
      (node (ref "P41") (pin "P$3") (pinfunction "P$1_P$3") (pintype "bidirectional"))
      (node (ref "R2") (pin "2") (pinfunction "2_2") (pintype "passive"))
      (node (ref "U1") (pin "C9") (pinfunction "GPIO53_C9") (pintype "bidirectional"))
    )
    (net (code "25") (name "AP4_GP55{slash}TT_BUZZER_GATE") (class "Default")
      (node (ref "P33") (pin "P$1") (pinfunction "P$1_P$1") (pintype "bidirectional"))
      (node (ref "P33") (pin "P$2") (pinfunction "P$1_P$2") (pintype "bidirectional"))
      (node (ref "P33") (pin "P$3") (pinfunction "P$1_P$3") (pintype "bidirectional"))
      (node (ref "U1") (pin "D9") (pinfunction "GPIO55_D9") (pintype "bidirectional"))
    )
    (net (code "26") (name "AP4_GP58{slash}TT_~{CHG}") (class "Default")
      (node (ref "P2") (pin "P$1") (pinfunction "P$1_P$1") (pintype "bidirectional"))
      (node (ref "P2") (pin "P$2") (pinfunction "P$1_P$2") (pintype "bidirectional"))
      (node (ref "P2") (pin "P$3") (pinfunction "P$1_P$3") (pintype "bidirectional"))
      (node (ref "U1") (pin "J7") (pinfunction "GPIO58_J7") (pintype "bidirectional"))
    )
    (net (code "27") (name "AP4_GP60{slash}TT_~{PG}") (class "Default")
      (node (ref "P3") (pin "P$1") (pinfunction "P$1_P$1") (pintype "bidirectional"))
      (node (ref "P3") (pin "P$2") (pinfunction "P$1_P$2") (pintype "bidirectional"))
      (node (ref "P3") (pin "P$3") (pinfunction "P$1_P$3") (pintype "bidirectional"))
      (node (ref "U1") (pin "K8") (pinfunction "GPIO60_K8") (pintype "bidirectional"))
    )
    (net (code "28") (name "AP4_GP63") (class "Default")
      (node (ref "P25") (pin "P$1") (pinfunction "P$1_P$1") (pintype "bidirectional"))
      (node (ref "P25") (pin "P$2") (pinfunction "P$1_P$2") (pintype "bidirectional"))
      (node (ref "P25") (pin "P$3") (pinfunction "P$1_P$3") (pintype "bidirectional"))
      (node (ref "U1") (pin "M6") (pinfunction "GPIO63_M6") (pintype "bidirectional"))
    )
    (net (code "29") (name "AP4_GP65{slash}TT_9DOF_~{RESET}") (class "Default")
      (node (ref "P45") (pin "P$1") (pinfunction "P$1_P$1") (pintype "bidirectional"))
      (node (ref "P45") (pin "P$2") (pinfunction "P$1_P$2") (pintype "bidirectional"))
      (node (ref "P45") (pin "P$3") (pinfunction "P$1_P$3") (pintype "bidirectional"))
      (node (ref "U1") (pin "A7") (pinfunction "GPIO65_A7") (pintype "bidirectional"))
    )
    (net (code "30") (name "AP4_GP66{slash}TT_QI_TS_CTRL") (class "Default")
      (node (ref "P44") (pin "P$1") (pinfunction "P$1_P$1") (pintype "bidirectional"))
      (node (ref "P44") (pin "P$2") (pinfunction "P$1_P$2") (pintype "bidirectional"))
      (node (ref "P44") (pin "P$3") (pinfunction "P$1_P$3") (pintype "bidirectional"))
      (node (ref "U1") (pin "A8") (pinfunction "GPIO66_A8") (pintype "bidirectional"))
    )
    (net (code "31") (name "AP4_GP69{slash}TT_FLASH_~{CS}") (class "Default")
      (node (ref "P42") (pin "P$1") (pinfunction "P$1_P$1") (pintype "bidirectional"))
      (node (ref "P42") (pin "P$2") (pinfunction "P$1_P$2") (pintype "bidirectional"))
      (node (ref "P42") (pin "P$3") (pinfunction "P$1_P$3") (pintype "bidirectional"))
      (node (ref "U1") (pin "B8") (pinfunction "GPIO69_B8") (pintype "bidirectional"))
    )
    (net (code "32") (name "AP4_GP72") (class "Default")
      (node (ref "P39") (pin "P$1") (pinfunction "P$1_P$1") (pintype "bidirectional"))
      (node (ref "P39") (pin "P$2") (pinfunction "P$1_P$2") (pintype "bidirectional"))
      (node (ref "P39") (pin "P$3") (pinfunction "P$1_P$3") (pintype "bidirectional"))
      (node (ref "U1") (pin "C8") (pinfunction "GPIO72_C8") (pintype "bidirectional"))
    )
    (net (code "33") (name "AP4_GP79") (class "Default")
      (node (ref "P22") (pin "P$1") (pinfunction "P$1_P$1") (pintype "bidirectional"))
      (node (ref "P22") (pin "P$2") (pinfunction "P$1_P$2") (pintype "bidirectional"))
      (node (ref "P22") (pin "P$3") (pinfunction "P$1_P$3") (pintype "bidirectional"))
      (node (ref "U1") (pin "M11") (pinfunction "GPIO79_M11") (pintype "bidirectional"))
    )
    (net (code "34") (name "AP4_GP80{slash}SWTRACE0") (class "Default")
      (node (ref "J2") (pin "2") (pinfunction "SWDIO_2") (pintype "bidirectional"))
      (node (ref "J2") (pin "B2") (pinfunction "SWDIO_B2") (pintype "bidirectional"))
      (node (ref "U1") (pin "K10") (pinfunction "GPIO80_K10") (pintype "bidirectional"))
    )
    (net (code "35") (name "AP4_GP81{slash}SWTRACE1") (class "Default")
      (node (ref "J2") (pin "4") (pinfunction "SWDCLK_4") (pintype "bidirectional"))
      (node (ref "J2") (pin "B4") (pinfunction "SWDCLK_B4") (pintype "bidirectional"))
      (node (ref "U1") (pin "L10") (pinfunction "GPIO81_L10") (pintype "bidirectional"))
    )
    (net (code "36") (name "AP4_GP82{slash}SWTRACE2") (class "Default")
      (node (ref "J2") (pin "6") (pinfunction "SWO_6") (pintype "bidirectional"))
      (node (ref "J2") (pin "B6") (pinfunction "SWO_B6") (pintype "bidirectional"))
      (node (ref "P18") (pin "P$1") (pinfunction "P$1_P$1") (pintype "bidirectional"))
      (node (ref "P18") (pin "P$2") (pinfunction "P$1_P$2") (pintype "bidirectional"))
      (node (ref "P18") (pin "P$3") (pinfunction "P$1_P$3") (pintype "bidirectional"))
      (node (ref "U1") (pin "L9") (pinfunction "GPIO82_L9") (pintype "bidirectional"))
    )
    (net (code "37") (name "AP4_GP83{slash}SWTRACE3") (class "Default")
      (node (ref "J2") (pin "3") (pinfunction "~{RESET}_3") (pintype "bidirectional"))
      (node (ref "J2") (pin "B3") (pinfunction "~{RESET}_B3") (pintype "bidirectional"))
      (node (ref "P19") (pin "P$1") (pinfunction "P$1_P$1") (pintype "bidirectional"))
      (node (ref "P19") (pin "P$2") (pinfunction "P$1_P$2") (pintype "bidirectional"))
      (node (ref "P19") (pin "P$3") (pinfunction "P$1_P$3") (pintype "bidirectional"))
      (node (ref "U1") (pin "K9") (pinfunction "GPIO83_K9") (pintype "bidirectional"))
    )
    (net (code "38") (name "AP4_GP88") (class "Default")
      (node (ref "P32") (pin "P$1") (pinfunction "P$1_P$1") (pintype "bidirectional"))
      (node (ref "P32") (pin "P$2") (pinfunction "P$1_P$2") (pintype "bidirectional"))
      (node (ref "P32") (pin "P$3") (pinfunction "P$1_P$3") (pintype "bidirectional"))
      (node (ref "U1") (pin "F9") (pinfunction "GPIO88_F9") (pintype "bidirectional"))
    )
    (net (code "39") (name "AP4_SWDCLK") (class "Default")
      (node (ref "J1") (pin "4") (pinfunction "SWDCLK_4") (pintype "bidirectional"))
      (node (ref "J1") (pin "B4") (pinfunction "SWDCLK_B4") (pintype "bidirectional"))
      (node (ref "U1") (pin "K3") (pinfunction "GPIO20_K3") (pintype "bidirectional"))
    )
    (net (code "40") (name "AP4_SWDIO") (class "Default")
      (node (ref "J1") (pin "2") (pinfunction "SWDIO_2") (pintype "bidirectional"))
      (node (ref "J1") (pin "B2") (pinfunction "SWDIO_B2") (pintype "bidirectional"))
      (node (ref "U1") (pin "J3") (pinfunction "GPIO21_J3") (pintype "bidirectional"))
    )
    (net (code "41") (name "AP4_SWO") (class "Default")
      (node (ref "J1") (pin "6") (pinfunction "SWO_6") (pintype "bidirectional"))
      (node (ref "J1") (pin "B6") (pinfunction "SWO_B6") (pintype "bidirectional"))
      (node (ref "U1") (pin "L4") (pinfunction "GPIO3_L4") (pintype "bidirectional"))
    )
    (net (code "42") (name "AP4_SWTRACECLK") (class "Default")
      (node (ref "J2") (pin "1") (pinfunction "VTREF_1") (pintype "bidirectional"))
      (node (ref "J2") (pin "B1") (pinfunction "VTREF_B1") (pintype "bidirectional"))
      (node (ref "U1") (pin "F12") (pinfunction "GPIO38_F12") (pintype "bidirectional"))
    )
    (net (code "43") (name "AP4_USB0_N") (class "Default")
      (node (ref "P21") (pin "P$1") (pinfunction "P$1_P$1") (pintype "bidirectional"))
      (node (ref "P21") (pin "P$2") (pinfunction "P$1_P$2") (pintype "bidirectional"))
      (node (ref "P21") (pin "P$3") (pinfunction "P$1_P$3") (pintype "bidirectional"))
      (node (ref "U1") (pin "M8") (pinfunction "USB0PN_M8") (pintype "bidirectional"))
    )
    (net (code "44") (name "AP4_USB0_P") (class "Default")
      (node (ref "P20") (pin "P$1") (pinfunction "P$1_P$1") (pintype "bidirectional"))
      (node (ref "P20") (pin "P$2") (pinfunction "P$1_P$2") (pintype "bidirectional"))
      (node (ref "P20") (pin "P$3") (pinfunction "P$1_P$3") (pintype "bidirectional"))
      (node (ref "U1") (pin "M7") (pinfunction "USB0PP_M7") (pintype "bidirectional"))
    )
    (net (code "45") (name "AP4_VDDBH") (class "Default")
      (node (ref "C25") (pin "1") (pinfunction "1_1") (pintype "bidirectional"))
      (node (ref "L2") (pin "2") (pinfunction "2_2") (pintype "bidirectional"))
      (node (ref "RZ1") (pin "1") (pinfunction "1_1") (pintype "passive"))
      (node (ref "TP1") (pin "P$1") (pinfunction "TESTPOINT_P$1") (pintype "bidirectional"))
      (node (ref "U1") (pin "G12") (pinfunction "VDDBH--BLE_BUCK_VOUT_G12") (pintype "bidirectional"))
    )
    (net (code "46") (name "AP4_VDDBH_RF") (class "Default")
      (node (ref "C12") (pin "P$1") (pinfunction "1_P$1") (pintype "bidirectional"))
      (node (ref "RZ1") (pin "2") (pinfunction "2_2") (pintype "passive"))
      (node (ref "U1") (pin "J1") (pinfunction "VDDBH_RF--BLE_BUCK_RF_VOUT_J1") (pintype "bidirectional"))
    )
    (net (code "47") (name "AP4_VDDF") (class "Default")
      (node (ref "C19") (pin "P$1") (pinfunction "1_P$1") (pintype "bidirectional"))
      (node (ref "C22") (pin "P$1") (pinfunction "1_P$1") (pintype "bidirectional"))
      (node (ref "TP3") (pin "P$1") (pinfunction "TESTPOINT_P$1") (pintype "bidirectional"))
      (node (ref "U1") (pin "C2") (pinfunction "VDDF-MEM_C2") (pintype "bidirectional"))
    )
    (net (code "48") (name "AP4_VDDMIPI_1P8") (class "Default")
      (node (ref "C14") (pin "P$1") (pinfunction "1_P$1") (pintype "bidirectional"))
      (node (ref "P28") (pin "P$1") (pinfunction "P$1_P$1") (pintype "bidirectional"))
      (node (ref "P28") (pin "P$2") (pinfunction "P$1_P$2") (pintype "bidirectional"))
      (node (ref "P28") (pin "P$3") (pinfunction "P$1_P$3") (pintype "bidirectional"))
      (node (ref "RZ4") (pin "1") (pinfunction "1_1") (pintype "passive"))
      (node (ref "U1") (pin "H10") (pinfunction "VDD18-MIPI_H10") (pintype "bidirectional"))
    )
    (net (code "49") (name "AP4_VDDUSB_0P9") (class "Default")
      (node (ref "C24") (pin "P$1") (pinfunction "1_P$1") (pintype "bidirectional"))
      (node (ref "P26") (pin "P$1") (pinfunction "P$1_P$1") (pintype "bidirectional"))
      (node (ref "P26") (pin "P$2") (pinfunction "P$1_P$2") (pintype "bidirectional"))
      (node (ref "P26") (pin "P$3") (pinfunction "P$1_P$3") (pintype "bidirectional"))
      (node (ref "RZ2") (pin "1") (pinfunction "1_1") (pintype "passive"))
      (node (ref "U1") (pin "L7") (pinfunction "VDDUSB0P9_L7") (pintype "bidirectional"))
    )
    (net (code "50") (name "AP4_VDDUSB_3P3") (class "Default")
      (node (ref "C13") (pin "P$1") (pinfunction "1_P$1") (pintype "bidirectional"))
      (node (ref "P27") (pin "P$1") (pinfunction "P$1_P$1") (pintype "bidirectional"))
      (node (ref "P27") (pin "P$2") (pinfunction "P$1_P$2") (pintype "bidirectional"))
      (node (ref "P27") (pin "P$3") (pinfunction "P$1_P$3") (pintype "bidirectional"))
      (node (ref "RZ3") (pin "1") (pinfunction "1_1") (pintype "passive"))
      (node (ref "U1") (pin "K7") (pinfunction "VDDUSB33_K7") (pintype "bidirectional"))
    )
    (net (code "51") (name "AP4_~{RESET}") (class "Default")
      (node (ref "C4") (pin "1") (pinfunction "1_1") (pintype "passive"))
      (node (ref "D1") (pin "1") (pinfunction "C_1") (pintype "passive"))
      (node (ref "J1") (pin "3") (pinfunction "~{RESET}_3") (pintype "bidirectional"))
      (node (ref "J1") (pin "B3") (pinfunction "~{RESET}_B3") (pintype "bidirectional"))
      (node (ref "P38") (pin "P$1") (pinfunction "P$1_P$1") (pintype "bidirectional"))
      (node (ref "P38") (pin "P$2") (pinfunction "P$1_P$2") (pintype "bidirectional"))
      (node (ref "P38") (pin "P$3") (pinfunction "P$1_P$3") (pintype "bidirectional"))
      (node (ref "SJ1") (pin "2") (pinfunction "2_2") (pintype "passive"))
      (node (ref "U1") (pin "A6") (pinfunction "~{RST}_A6") (pintype "input"))
    )
    (net (code "52") (name "BLE_RFOUT") (class "Default")
      (node (ref "P15") (pin "P$1") (pinfunction "P$1_P$1") (pintype "bidirectional"))
      (node (ref "P15") (pin "P$2") (pinfunction "P$1_P$2") (pintype "bidirectional"))
      (node (ref "P15") (pin "P$3") (pinfunction "P$1_P$3") (pintype "bidirectional"))
      (node (ref "S4") (pin "OUT") (pinfunction "A_OUT") (pintype "bidirectional"))
    )
    (net (code "53") (name "GND") (class "Default")
      (node (ref "C10") (pin "P$2") (pinfunction "2_P$2") (pintype "bidirectional"))
      (node (ref "C11") (pin "P$1") (pinfunction "1_P$1") (pintype "bidirectional"))
      (node (ref "C13") (pin "P$2") (pinfunction "2_P$2") (pintype "bidirectional"))
      (node (ref "C14") (pin "P$2") (pinfunction "2_P$2") (pintype "bidirectional"))
      (node (ref "C15") (pin "P$2") (pinfunction "2_P$2") (pintype "bidirectional"))
      (node (ref "C16") (pin "P$2") (pinfunction "2_P$2") (pintype "bidirectional"))
      (node (ref "C17") (pin "P$2") (pinfunction "2_P$2") (pintype "bidirectional"))
      (node (ref "C18") (pin "P$2") (pinfunction "2_P$2") (pintype "bidirectional"))
      (node (ref "C19") (pin "P$2") (pinfunction "2_P$2") (pintype "bidirectional"))
      (node (ref "C2") (pin "2") (pinfunction "2_2") (pintype "passive"))
      (node (ref "C20") (pin "P$2") (pinfunction "2_P$2") (pintype "bidirectional"))
      (node (ref "C21") (pin "P$2") (pinfunction "2_P$2") (pintype "bidirectional"))
      (node (ref "C23") (pin "P$1") (pinfunction "1_P$1") (pintype "bidirectional"))
      (node (ref "C24") (pin "P$2") (pinfunction "2_P$2") (pintype "bidirectional"))
      (node (ref "C25") (pin "2") (pinfunction "2_2") (pintype "bidirectional"))
      (node (ref "C3") (pin "2") (pinfunction "2_2") (pintype "passive"))
      (node (ref "C4") (pin "2") (pinfunction "2_2") (pintype "passive"))
      (node (ref "C5") (pin "P$2") (pinfunction "2_P$2") (pintype "bidirectional"))
      (node (ref "C6") (pin "P$2") (pinfunction "2_P$2") (pintype "bidirectional"))
      (node (ref "C7") (pin "P$2") (pinfunction "2_P$2") (pintype "bidirectional"))
      (node (ref "C8") (pin "P$2") (pinfunction "2_P$2") (pintype "bidirectional"))
      (node (ref "C9") (pin "P$2") (pinfunction "2_P$2") (pintype "bidirectional"))
      (node (ref "CX1") (pin "2") (pinfunction "2_2") (pintype "passive"))
      (node (ref "CX2") (pin "2") (pinfunction "2_2") (pintype "passive"))
      (node (ref "D1") (pin "2") (pinfunction "A_2") (pintype "passive"))
      (node (ref "J1") (pin "5") (pinfunction "GND_5") (pintype "bidirectional"))
      (node (ref "J1") (pin "B5") (pinfunction "GND_B5") (pintype "bidirectional"))
      (node (ref "J2") (pin "5") (pinfunction "GND_5") (pintype "bidirectional"))
      (node (ref "J2") (pin "B5") (pinfunction "GND_B5") (pintype "bidirectional"))
      (node (ref "P13") (pin "P$1") (pinfunction "P$1_P$1") (pintype "bidirectional"))
      (node (ref "P13") (pin "P$2") (pinfunction "P$1_P$2") (pintype "bidirectional"))
      (node (ref "P13") (pin "P$3") (pinfunction "P$1_P$3") (pintype "bidirectional"))
      (node (ref "P37") (pin "P$1") (pinfunction "P$1_P$1") (pintype "bidirectional"))
      (node (ref "P37") (pin "P$2") (pinfunction "P$1_P$2") (pintype "bidirectional"))
      (node (ref "P37") (pin "P$3") (pinfunction "P$1_P$3") (pintype "bidirectional"))
      (node (ref "RZ2") (pin "2") (pinfunction "2_2") (pintype "passive"))
      (node (ref "RZ3") (pin "2") (pinfunction "2_2") (pintype "passive"))
      (node (ref "RZ4") (pin "2") (pinfunction "2_2") (pintype "passive"))
      (node (ref "SJ1") (pin "1") (pinfunction "1_1") (pintype "passive"))
      (node (ref "U1") (pin "B12") (pinfunction "VSSAUDA_B12") (pintype "bidirectional"))
      (node (ref "U1") (pin "B2") (pinfunction "VSSP-BUCK_REGS_GND_B2") (pintype "bidirectional"))
      (node (ref "U1") (pin "B5") (pinfunction "VSSA-ANALOG_GND_B5") (pintype "bidirectional"))
      (node (ref "U1") (pin "D2") (pinfunction "VSS-DGND_FOR_VDDF_AND_PADS_D2") (pintype "bidirectional"))
      (node (ref "U1") (pin "E12") (pinfunction "VSSAUDD_E12") (pintype "bidirectional"))
      (node (ref "U1") (pin "H1") (pinfunction "VSSB-BLE_UNREG_GND_H1") (pintype "bidirectional"))
      (node (ref "U1") (pin "J10") (pinfunction "VSS18-MIPI_J10") (pintype "bidirectional"))
      (node (ref "U1") (pin "L1") (pinfunction "VSSVCO-BLECORE_GND_FOR_VCO_L1") (pintype "bidirectional"))
      (node (ref "U1") (pin "L2") (pinfunction "VSSS-HVSIMOBUCK_GND_L2") (pintype "bidirectional"))
      (node (ref "U1") (pin "L8") (pinfunction "VSSAUSB_L8") (pintype "bidirectional"))
      (node (ref "VR2") (pin "2") (pinfunction "GND_2") (pintype "bidirectional"))
      (node (ref "VR2") (pin "PAD") (pinfunction "GND_PAD") (pintype "bidirectional"))
      (node (ref "X2") (pin "2") (pinfunction "GND_2") (pintype "bidirectional"))
      (node (ref "X2") (pin "4") (pinfunction "GND_4") (pintype "bidirectional"))
    )
    (net (code "54") (name "Net-(C1-Pad1)") (class "Default")
      (node (ref "C1") (pin "1") (pinfunction "1_1") (pintype "passive"))
      (node (ref "L3") (pin "2") (pinfunction "2_2") (pintype "passive"))
      (node (ref "L4") (pin "1") (pinfunction "1_1") (pintype "passive"))
    )
    (net (code "55") (name "Net-(C6-1)") (class "Default")
      (node (ref "C6") (pin "P$1") (pinfunction "1_P$1") (pintype "bidirectional"))
      (node (ref "RZ6") (pin "1") (pinfunction "1_1") (pintype "passive"))
      (node (ref "VR2") (pin "1") (pinfunction "OUT_1") (pintype "power_in"))
    )
    (net (code "56") (name "Net-(C11-2)") (class "Default")
      (node (ref "C11") (pin "P$2") (pinfunction "2_P$2") (pintype "bidirectional"))
      (node (ref "U1") (pin "A12") (pinfunction "LPADC_VREF_A12") (pintype "bidirectional"))
    )
    (net (code "57") (name "Net-(C16-1)") (class "Default")
      (node (ref "C16") (pin "P$1") (pinfunction "1_P$1") (pintype "bidirectional"))
      (node (ref "U1") (pin "C1") (pinfunction "VDDS-SRAM_HV_SUP_C1") (pintype "bidirectional"))
    )
    (net (code "58") (name "Net-(C17-1)") (class "Default")
      (node (ref "C17") (pin "P$1") (pinfunction "1_P$1") (pintype "bidirectional"))
      (node (ref "U1") (pin "A3") (pinfunction "VDDC-CORE_A3") (pintype "bidirectional"))
    )
    (net (code "59") (name "Net-(C18-1)") (class "Default")
      (node (ref "C18") (pin "P$1") (pinfunction "1_P$1") (pintype "bidirectional"))
      (node (ref "U1") (pin "B3") (pinfunction "VDDC_LV-CORE_LV_B3") (pintype "bidirectional"))
    )
    (net (code "60") (name "Net-(C23-2)") (class "Default")
      (node (ref "C23") (pin "P$2") (pinfunction "2_P$2") (pintype "bidirectional"))
      (node (ref "U1") (pin "B10") (pinfunction "LPMICBIAS_B10") (pintype "output"))
    )
    (net (code "61") (name "Net-(D2-PadC1)") (class "Default")
      (node (ref "D2") (pin "C1") (pinfunction "C1_C1") (pintype "bidirectional"))
      (node (ref "R2") (pin "1") (pinfunction "1_1") (pintype "passive"))
    )
    (net (code "62") (name "Net-(D2-PadC2)") (class "Default")
      (node (ref "D2") (pin "C2") (pinfunction "C2_C2") (pintype "bidirectional"))
      (node (ref "R1") (pin "1") (pinfunction "1_1") (pintype "passive"))
    )
    (net (code "63") (name "Net-(L1-1)") (class "Default")
      (node (ref "L1") (pin "P$1") (pinfunction "1_P$1") (pintype "bidirectional"))
      (node (ref "U1") (pin "A1") (pinfunction "SIMOBUCK_SW_A1") (pintype "bidirectional"))
    )
    (net (code "64") (name "Net-(L1-2)") (class "Default")
      (node (ref "L1") (pin "P$2") (pinfunction "2_P$2") (pintype "bidirectional"))
      (node (ref "U1") (pin "A2") (pinfunction "SIMOBUCK_SWSEL_A2") (pintype "bidirectional"))
    )
    (net (code "65") (name "Net-(L4-Pad2)") (class "Default")
      (node (ref "L4") (pin "2") (pinfunction "2_2") (pintype "passive"))
      (node (ref "S4") (pin "IN") (pinfunction "IN_IN") (pintype "bidirectional"))
    )
    (net (code "66") (name "Net-(U1-RFIOP)") (class "Default")
      (node (ref "CX5") (pin "1") (pinfunction "1_1") (pintype "passive"))
      (node (ref "L3") (pin "1") (pinfunction "1_1") (pintype "passive"))
      (node (ref "U1") (pin "M2") (pinfunction "RFIOP_M2") (pintype "bidirectional"))
    )
    (net (code "67") (name "Net-(U1-VDDBH_SW--BLE_BUCK_SW)") (class "Default")
      (node (ref "L2") (pin "1") (pinfunction "1_1") (pintype "bidirectional"))
      (node (ref "U1") (pin "H12") (pinfunction "VDDBH_SW--BLE_BUCK_SW_H12") (pintype "bidirectional"))
    )
    (net (code "68") (name "Net-(U1-XI)") (class "Default")
      (node (ref "C3") (pin "1") (pinfunction "1_1") (pintype "passive"))
      (node (ref "U1") (pin "A4") (pinfunction "XI_A4") (pintype "bidirectional"))
      (node (ref "X1") (pin "2") (pinfunction "2_2") (pintype "bidirectional"))
    )
    (net (code "69") (name "Net-(U1-XI32M)") (class "Default")
      (node (ref "CX2") (pin "1") (pinfunction "1_1") (pintype "passive"))
      (node (ref "U1") (pin "C12") (pinfunction "XI32M_C12") (pintype "bidirectional"))
      (node (ref "X2") (pin "3") (pinfunction "2_3") (pintype "bidirectional"))
    )
    (net (code "70") (name "Net-(U1-XO)") (class "Default")
      (node (ref "C2") (pin "1") (pinfunction "1_1") (pintype "passive"))
      (node (ref "U1") (pin "A5") (pinfunction "XO_A5") (pintype "bidirectional"))
      (node (ref "X1") (pin "1") (pinfunction "1_1") (pintype "bidirectional"))
    )
    (net (code "71") (name "Net-(U1-XO32M)") (class "Default")
      (node (ref "CX1") (pin "1") (pinfunction "1_1") (pintype "passive"))
      (node (ref "U1") (pin "D12") (pinfunction "XO32M_D12") (pintype "bidirectional"))
      (node (ref "X2") (pin "1") (pinfunction "1_1") (pintype "bidirectional"))
    )
    (net (code "72") (name "Net-(VR2-EN)") (class "Default")
      (node (ref "RZ5") (pin "2") (pinfunction "2_2") (pintype "passive"))
      (node (ref "VR2") (pin "3") (pinfunction "EN_3") (pintype "input"))
    )
    (net (code "73") (name "VDD") (class "Default")
      (node (ref "C5") (pin "P$1") (pinfunction "1_P$1") (pintype "bidirectional"))
      (node (ref "P29") (pin "P$1") (pinfunction "P$1_P$1") (pintype "bidirectional"))
      (node (ref "P29") (pin "P$2") (pinfunction "P$1_P$2") (pintype "bidirectional"))
      (node (ref "P29") (pin "P$3") (pinfunction "P$1_P$3") (pintype "bidirectional"))
      (node (ref "RZ5") (pin "1") (pinfunction "1_1") (pintype "passive"))
      (node (ref "VR2") (pin "4") (pinfunction "IN_4") (pintype "bidirectional"))
    )
    (net (code "74") (name "VDDAUDA_1P8-CLEAN") (class "Default")
      (node (ref "C15") (pin "P$1") (pinfunction "1_P$1") (pintype "bidirectional"))
      (node (ref "RZ6") (pin "2") (pinfunction "2_2") (pintype "passive"))
      (node (ref "U1") (pin "B11") (pinfunction "VDDAUDA_B11") (pintype "bidirectional"))
    )
    (net (code "75") (name "unconnected-(U1-GPIO0-PadH3)") (class "Default")
      (node (ref "U1") (pin "H3") (pinfunction "GPIO0_H3") (pintype "bidirectional"))
    )
    (net (code "76") (name "unconnected-(U1-GPIO1-PadJ4)") (class "Default")
      (node (ref "U1") (pin "J4") (pinfunction "GPIO1_J4") (pintype "bidirectional"))
    )
    (net (code "77") (name "unconnected-(U1-GPIO2-PadK4)") (class "Default")
      (node (ref "U1") (pin "K4") (pinfunction "GPIO2_K4") (pintype "bidirectional"))
    )
    (net (code "78") (name "unconnected-(U1-GPIO4-PadM4)") (class "Default")
      (node (ref "U1") (pin "M4") (pinfunction "GPIO4_M4") (pintype "bidirectional"))
    )
    (net (code "79") (name "unconnected-(U1-GPIO5-PadH4)") (class "Default")
      (node (ref "U1") (pin "H4") (pinfunction "GPIO5_H4") (pintype "bidirectional"))
    )
    (net (code "80") (name "unconnected-(U1-GPIO7-PadJ6)") (class "Default")
      (node (ref "U1") (pin "J6") (pinfunction "GPIO7_J6") (pintype "bidirectional"))
    )
    (net (code "81") (name "unconnected-(U1-GPIO10-PadE6)") (class "Default")
      (node (ref "U1") (pin "E6") (pinfunction "GPIO10_E6") (pintype "bidirectional"))
    )
    (net (code "82") (name "unconnected-(U1-GPIO11-PadE4)") (class "Default")
      (node (ref "U1") (pin "E4") (pinfunction "GPIO11_E4") (pintype "bidirectional"))
    )
    (net (code "83") (name "unconnected-(U1-GPIO12-PadB4)") (class "Default")
      (node (ref "U1") (pin "B4") (pinfunction "GPIO12_B4") (pintype "bidirectional"))
    )
    (net (code "84") (name "unconnected-(U1-GPIO15-PadE5)") (class "Default")
      (node (ref "U1") (pin "E5") (pinfunction "GPIO15_E5") (pintype "bidirectional"))
    )
    (net (code "85") (name "unconnected-(U1-GPIO16-PadD7)") (class "Default")
      (node (ref "U1") (pin "D7") (pinfunction "GPIO16_D7") (pintype "bidirectional"))
    )
    (net (code "86") (name "unconnected-(U1-GPIO19-PadC3)") (class "Default")
      (node (ref "U1") (pin "C3") (pinfunction "GPIO19_C3") (pintype "bidirectional"))
    )
    (net (code "87") (name "unconnected-(U1-GPIO22-PadF3)") (class "Default")
      (node (ref "U1") (pin "F3") (pinfunction "GPIO22_F3") (pintype "bidirectional"))
    )
    (net (code "88") (name "unconnected-(U1-GPIO23-PadF2)") (class "Default")
      (node (ref "U1") (pin "F2") (pinfunction "GPIO23_F2") (pintype "bidirectional"))
    )
    (net (code "89") (name "unconnected-(U1-GPIO28-PadE3)") (class "Default")
      (node (ref "U1") (pin "E3") (pinfunction "GPIO28_E3") (pintype "bidirectional"))
    )
    (net (code "90") (name "unconnected-(U1-GPIO37-PadF11)") (class "Default")
      (node (ref "U1") (pin "F11") (pinfunction "GPIO37_F11") (pintype "bidirectional"))
    )
    (net (code "91") (name "unconnected-(U1-GPIO52-PadC10)") (class "Default")
      (node (ref "U1") (pin "C10") (pinfunction "GPIO52_C10") (pintype "bidirectional"))
    )
    (net (code "92") (name "unconnected-(U1-GPIO54-PadD10)") (class "Default")
      (node (ref "U1") (pin "D10") (pinfunction "GPIO54_D10") (pintype "bidirectional"))
    )
    (net (code "93") (name "unconnected-(U1-GPIO56-PadE10)") (class "Default")
      (node (ref "U1") (pin "E10") (pinfunction "GPIO56_E10") (pintype "bidirectional"))
    )
    (net (code "94") (name "unconnected-(U1-GPIO57-PadE9)") (class "Default")
      (node (ref "U1") (pin "E9") (pinfunction "GPIO57_E9") (pintype "bidirectional"))
    )
    (net (code "95") (name "unconnected-(U1-GPIO59-PadJ8)") (class "Default")
      (node (ref "U1") (pin "J8") (pinfunction "GPIO59_J8") (pintype "bidirectional"))
    )
    (net (code "96") (name "unconnected-(U1-GPIO61-PadK6)") (class "Default")
      (node (ref "U1") (pin "K6") (pinfunction "GPIO61_K6") (pintype "bidirectional"))
    )
    (net (code "97") (name "unconnected-(U1-GPIO62-PadL6)") (class "Default")
      (node (ref "U1") (pin "L6") (pinfunction "GPIO62_L6") (pintype "bidirectional"))
    )
    (net (code "98") (name "unconnected-(U1-GPIO64-PadB6)") (class "Default")
      (node (ref "U1") (pin "B6") (pinfunction "GPIO64_B6") (pintype "bidirectional"))
    )
    (net (code "99") (name "unconnected-(U1-GPIO67-PadC6)") (class "Default")
      (node (ref "U1") (pin "C6") (pinfunction "GPIO67_C6") (pintype "bidirectional"))
    )
    (net (code "100") (name "unconnected-(U1-GPIO68-PadB7)") (class "Default")
      (node (ref "U1") (pin "B7") (pinfunction "GPIO68_B7") (pintype "bidirectional"))
    )
    (net (code "101") (name "unconnected-(U1-GPIO70-PadC5)") (class "Default")
      (node (ref "U1") (pin "C5") (pinfunction "GPIO70_C5") (pintype "bidirectional"))
    )
    (net (code "102") (name "unconnected-(U1-GPIO71-PadC7)") (class "Default")
      (node (ref "U1") (pin "C7") (pinfunction "GPIO71_C7") (pintype "bidirectional"))
    )
    (net (code "103") (name "unconnected-(U1-GPIO73-PadD8)") (class "Default")
      (node (ref "U1") (pin "D8") (pinfunction "GPIO73_D8") (pintype "bidirectional"))
    )
    (net (code "104") (name "unconnected-(U1-GPIO74-PadG11)") (class "Default")
      (node (ref "U1") (pin "G11") (pinfunction "GPIO74_G11") (pintype "bidirectional"))
    )
    (net (code "105") (name "unconnected-(U1-GPIO75-PadH11)") (class "Default")
      (node (ref "U1") (pin "H11") (pinfunction "GPIO75_H11") (pintype "bidirectional"))
    )
    (net (code "106") (name "unconnected-(U1-GPIO76-PadJ11)") (class "Default")
      (node (ref "U1") (pin "J11") (pinfunction "GPIO76_J11") (pintype "bidirectional"))
    )
    (net (code "107") (name "unconnected-(U1-GPIO77-PadK11)") (class "Default")
      (node (ref "U1") (pin "K11") (pinfunction "GPIO77_K11") (pintype "bidirectional"))
    )
    (net (code "108") (name "unconnected-(U1-GPIO78-PadL11)") (class "Default")
      (node (ref "U1") (pin "L11") (pinfunction "GPIO78_L11") (pintype "bidirectional"))
    )
    (net (code "109") (name "unconnected-(U1-GPIO84-PadJ9)") (class "Default")
      (node (ref "U1") (pin "J9") (pinfunction "GPIO84_J9") (pintype "bidirectional"))
    )
    (net (code "110") (name "unconnected-(U1-GPIO85-PadH9)") (class "Default")
      (node (ref "U1") (pin "H9") (pinfunction "GPIO85_H9") (pintype "bidirectional"))
    )
    (net (code "111") (name "unconnected-(U1-GPIO86-PadG10)") (class "Default")
      (node (ref "U1") (pin "G10") (pinfunction "GPIO86_G10") (pintype "bidirectional"))
    )
    (net (code "112") (name "unconnected-(U1-GPIO87-PadG9)") (class "Default")
      (node (ref "U1") (pin "G9") (pinfunction "GPIO87_G9") (pintype "bidirectional"))
    )
    (net (code "113") (name "unconnected-(U1-GPIO89-PadF10)") (class "Default")
      (node (ref "U1") (pin "F10") (pinfunction "GPIO89_F10") (pintype "bidirectional"))
    )
    (net (code "114") (name "unconnected-(U1-GPIO90-PadJ2)") (class "Default")
      (node (ref "U1") (pin "J2") (pinfunction "GPIO90_J2") (pintype "bidirectional"))
    )
    (net (code "115") (name "unconnected-(U1-GPIO91-PadK2)") (class "Default")
      (node (ref "U1") (pin "K2") (pinfunction "GPIO91_K2") (pintype "bidirectional"))
    )
    (net (code "116") (name "unconnected-(U1-LPADC_D0NSE0-PadA10)") (class "Default")
      (node (ref "U1") (pin "A10") (pinfunction "LPADC_D0NSE0_A10") (pintype "input"))
    )
    (net (code "117") (name "unconnected-(U1-LPADC_D0PSE1-PadA11)") (class "Default")
      (node (ref "U1") (pin "A11") (pinfunction "LPADC_D0PSE1_A11") (pintype "input"))
    )
    (net (code "118") (name "unconnected-(U1-LPADC_D1NSE2-PadC11)") (class "Default")
      (node (ref "U1") (pin "C11") (pinfunction "LPADC_D1NSE2_C11") (pintype "input"))
    )
    (net (code "119") (name "unconnected-(U1-LPADC_D1PSE3-PadD11)") (class "Default")
      (node (ref "U1") (pin "D11") (pinfunction "LPADC_D1PSE3_D11") (pintype "input"))
    )
    (net (code "120") (name "unconnected-(U1-MIPI_CLKN-PadJ12)") (class "Default")
      (node (ref "U1") (pin "J12") (pinfunction "MIPI_CLKN_J12") (pintype "bidirectional"))
    )
    (net (code "121") (name "unconnected-(U1-MIPI_CLKP-PadK12)") (class "Default")
      (node (ref "U1") (pin "K12") (pinfunction "MIPI_CLKP_K12") (pintype "bidirectional"))
    )
    (net (code "122") (name "unconnected-(U1-MIPI_DON-PadL12)") (class "Default")
      (node (ref "U1") (pin "L12") (pinfunction "MIPI_DON_L12") (pintype "bidirectional"))
    )
    (net (code "123") (name "unconnected-(U1-MIPI_DOP-PadM12)") (class "Default")
      (node (ref "U1") (pin "M12") (pinfunction "MIPI_DOP_M12") (pintype "bidirectional"))
    )
    (net (code "124") (name "unconnected-(U1-TXEN-PadK1)") (class "Default")
      (node (ref "U1") (pin "K1") (pinfunction "TXEN_K1") (pintype "output"))
    )
  )
)
